# reegan-brd.net
KiCad netlist of a schematic drawn in EAGLE
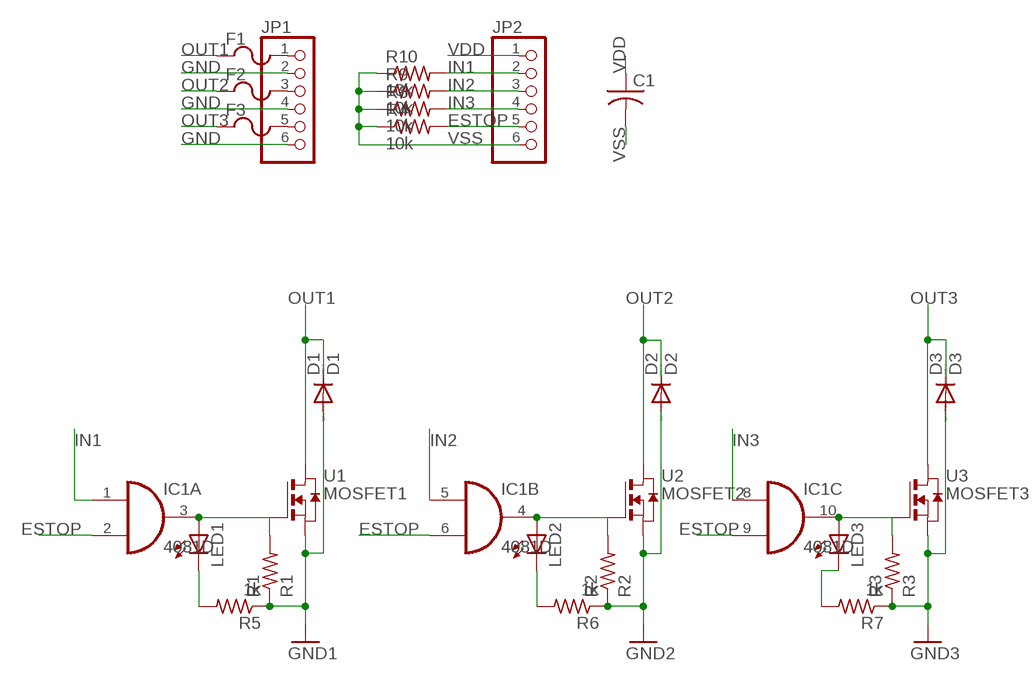
[diagram p0: schematic, sheet 1]

(export (version "E")
  (design (tool "Eeschema 10.0.6"))
  (components
    (comp (ref "C1")
      (value "C-USC0603")
      (footprint "eagle-import:C0603")
      (libsource (lib "eagle-import") (part "C-USC0603"))
    )
    (comp (ref "D1")
      (value "D1")
      (footprint "eagle-import:DO41-10")
      (libsource (lib "eagle-import") (part "1N4004"))
    )
    (comp (ref "D2")
      (value "D2")
      (footprint "eagle-import:DO41-10")
      (libsource (lib "eagle-import") (part "1N4004"))
    )
    (comp (ref "D3")
      (value "D3")
      (footprint "eagle-import:DO41-10")
      (libsource (lib "eagle-import") (part "1N4004"))
    )
    (comp (ref "F1")
      (value "POLYFUSE")
      (footprint "eagle-import:1206")
      (libsource (lib "eagle-import") (part "POLYFUSE"))
    )
    (comp (ref "F2")
      (value "POLYFUSE")
      (footprint "eagle-import:1206")
      (libsource (lib "eagle-import") (part "POLYFUSE"))
    )
    (comp (ref "F3")
      (value "POLYFUSE")
      (footprint "eagle-import:1206")
      (libsource (lib "eagle-import") (part "POLYFUSE"))
    )
    (comp (ref "IC1")
      (value "4081D")
      (footprint "eagle-import:SO14")
      (libsource (lib "eagle-import") (part "4081D"))
    )
    (comp (ref "JP1")
      (value "PINHD-1X6")
      (footprint "eagle-import:1X06")
      (libsource (lib "eagle-import") (part "PINHD-1X6"))
    )
    (comp (ref "JP2")
      (value "PINHD-1X6")
      (footprint "eagle-import:1X06")
      (libsource (lib "eagle-import") (part "PINHD-1X6"))
    )
    (comp (ref "LED1")
      (value "LEDCHIPLED_0603")
      (footprint "eagle-import:CHIPLED_0603")
      (libsource (lib "eagle-import") (part "LEDCHIPLED_0603"))
    )
    (comp (ref "LED2")
      (value "LEDCHIPLED_0603")
      (footprint "eagle-import:CHIPLED_0603")
      (libsource (lib "eagle-import") (part "LEDCHIPLED_0603"))
    )
    (comp (ref "LED3")
      (value "LEDCHIPLED_0603")
      (footprint "eagle-import:CHIPLED_0603")
      (libsource (lib "eagle-import") (part "LEDCHIPLED_0603"))
    )
    (comp (ref "R1")
      (value "R1")
      (footprint "eagle-import:R0603")
      (libsource (lib "eagle-import") (part "resistor_R-US_R0603"))
    )
    (comp (ref "R2")
      (value "R2")
      (footprint "eagle-import:R0603")
      (libsource (lib "eagle-import") (part "resistor_R-US_R0603"))
    )
    (comp (ref "R3")
      (value "R3")
      (footprint "eagle-import:R0603")
      (libsource (lib "eagle-import") (part "resistor_R-US_R0603"))
    )
    (comp (ref "R4")
      (value "10k")
      (footprint "eagle-import:R0603")
      (libsource (lib "eagle-import") (part "R-US_R0603"))
    )
    (comp (ref "R5")
      (value "1k")
      (footprint "eagle-import:R0603")
      (libsource (lib "eagle-import") (part "resistor_R-US_R0603"))
    )
    (comp (ref "R6")
      (value "1k")
      (footprint "eagle-import:R0603")
      (libsource (lib "eagle-import") (part "resistor_R-US_R0603"))
    )
    (comp (ref "R7")
      (value "1k")
      (footprint "eagle-import:R0603")
      (libsource (lib "eagle-import") (part "resistor_R-US_R0603"))
    )
    (comp (ref "R8")
      (value "10k")
      (footprint "eagle-import:R0603")
      (libsource (lib "eagle-import") (part "R-US_R0603"))
    )
    (comp (ref "R9")
      (value "10k")
      (footprint "eagle-import:R0603")
      (libsource (lib "eagle-import") (part "R-US_R0603"))
    )
    (comp (ref "R10")
      (value "10k")
      (footprint "eagle-import:R0603")
      (libsource (lib "eagle-import") (part "R-US_R0603"))
    )
    (comp (ref "U1")
      (value "MOSFET1")
      (footprint "eagle-import:MOSFET")
      (libsource (lib "eagle-import") (part "MOSFET"))
    )
    (comp (ref "U2")
      (value "MOSFET2")
      (footprint "eagle-import:MOSFET")
      (libsource (lib "eagle-import") (part "MOSFET"))
    )
    (comp (ref "U3")
      (value "MOSFET3")
      (footprint "eagle-import:MOSFET")
      (libsource (lib "eagle-import") (part "MOSFET"))
    )
  )
  (nets
    (net (code "1") (name "/ESTOP") (class "Default")
      (node (ref "IC1") (pin "2") (pinfunction "I1_2") (pintype "input"))
      (node (ref "IC1") (pin "6") (pinfunction "I1_6") (pintype "input"))
      (node (ref "IC1") (pin "9") (pinfunction "I1_9") (pintype "input"))
      (node (ref "JP2") (pin "5") (pinfunction "5_5") (pintype "passive"))
      (node (ref "R4") (pin "2") (pinfunction "2_2") (pintype "passive"))
    )
    (net (code "2") (name "/IN1") (class "Default")
      (node (ref "IC1") (pin "1") (pinfunction "I0_1") (pintype "input"))
      (node (ref "JP2") (pin "2") (pinfunction "2_2") (pintype "passive"))
      (node (ref "R10") (pin "2") (pinfunction "2_2") (pintype "passive"))
    )
    (net (code "3") (name "/IN2") (class "Default")
      (node (ref "IC1") (pin "5") (pinfunction "I0_5") (pintype "input"))
      (node (ref "JP2") (pin "3") (pinfunction "3_3") (pintype "passive"))
      (node (ref "R9") (pin "2") (pinfunction "2_2") (pintype "passive"))
    )
    (net (code "4") (name "/IN3") (class "Default")
      (node (ref "IC1") (pin "8") (pinfunction "I0_8") (pintype "input"))
      (node (ref "JP2") (pin "4") (pinfunction "4_4") (pintype "passive"))
      (node (ref "R8") (pin "2") (pinfunction "2_2") (pintype "passive"))
    )
    (net (code "5") (name "/OUT1") (class "Default")
      (node (ref "D1") (pin "C") (pinfunction "C_C") (pintype "passive"))
      (node (ref "F1") (pin "1") (pinfunction "1_1") (pintype "passive"))
      (node (ref "U1") (pin "P$2") (pinfunction "D_P$2") (pintype "passive"))
    )
    (net (code "6") (name "/OUT2") (class "Default")
      (node (ref "D2") (pin "C") (pinfunction "C_C") (pintype "passive"))
      (node (ref "F2") (pin "1") (pinfunction "1_1") (pintype "passive"))
      (node (ref "U2") (pin "P$2") (pinfunction "D_P$2") (pintype "passive"))
    )
    (net (code "7") (name "/OUT3") (class "Default")
      (node (ref "D3") (pin "C") (pinfunction "C_C") (pintype "passive"))
      (node (ref "F3") (pin "1") (pinfunction "1_1") (pintype "passive"))
      (node (ref "U3") (pin "P$2") (pinfunction "D_P$2") (pintype "passive"))
    )
    (net (code "8") (name "/VDD") (class "Default")
      (node (ref "C1") (pin "1") (pinfunction "1_1") (pintype "passive"))
      (node (ref "JP2") (pin "1") (pinfunction "1_1") (pintype "passive"))
    )
    (net (code "9") (name "/VSS") (class "Default")
      (node (ref "C1") (pin "2") (pinfunction "2_2") (pintype "passive"))
      (node (ref "JP2") (pin "6") (pinfunction "6_6") (pintype "passive"))
      (node (ref "R10") (pin "1") (pinfunction "1_1") (pintype "passive"))
      (node (ref "R4") (pin "1") (pinfunction "1_1") (pintype "passive"))
      (node (ref "R8") (pin "1") (pinfunction "1_1") (pintype "passive"))
      (node (ref "R9") (pin "1") (pinfunction "1_1") (pintype "passive"))
    )
    (net (code "10") (name "GND1") (class "Default")
      (node (ref "D1") (pin "A") (pinfunction "A_A") (pintype "passive"))
      (node (ref "D2") (pin "A") (pinfunction "A_A") (pintype "passive"))
      (node (ref "D3") (pin "A") (pinfunction "A_A") (pintype "passive"))
      (node (ref "JP1") (pin "2") (pinfunction "2_2") (pintype "passive"))
      (node (ref "JP1") (pin "4") (pinfunction "4_4") (pintype "passive"))
      (node (ref "JP1") (pin "6") (pinfunction "6_6") (pintype "passive"))
      (node (ref "R1") (pin "1") (pinfunction "1_1") (pintype "passive"))
      (node (ref "R2") (pin "1") (pinfunction "1_1") (pintype "passive"))
      (node (ref "R3") (pin "1") (pinfunction "1_1") (pintype "passive"))
      (node (ref "R5") (pin "1") (pinfunction "1_1") (pintype "passive"))
      (node (ref "R6") (pin "1") (pinfunction "1_1") (pintype "passive"))
      (node (ref "R7") (pin "1") (pinfunction "1_1") (pintype "passive"))
      (node (ref "U1") (pin "P$3") (pinfunction "S_P$3") (pintype "passive"))
      (node (ref "U2") (pin "P$3") (pinfunction "S_P$3") (pintype "passive"))
      (node (ref "U3") (pin "P$3") (pinfunction "S_P$3") (pintype "passive"))
    )
    (net (code "11") (name "Net-(F1-Pad2)") (class "Default")
      (node (ref "F1") (pin "2") (pinfunction "2_2") (pintype "passive"))
      (node (ref "JP1") (pin "1") (pinfunction "1_1") (pintype "passive"))
    )
    (net (code "12") (name "Net-(F2-Pad2)") (class "Default")
      (node (ref "F2") (pin "2") (pinfunction "2_2") (pintype "passive"))
      (node (ref "JP1") (pin "3") (pinfunction "3_3") (pintype "passive"))
    )
    (net (code "13") (name "Net-(F3-Pad2)") (class "Default")
      (node (ref "F3") (pin "2") (pinfunction "2_2") (pintype "passive"))
      (node (ref "JP1") (pin "5") (pinfunction "5_5") (pintype "passive"))
    )
    (net (code "14") (name "Net-(IC1A-O)") (class "Default")
      (node (ref "IC1") (pin "3") (pinfunction "O_3") (pintype "output"))
      (node (ref "LED1") (pin "A") (pinfunction "A_A") (pintype "passive"))
      (node (ref "R1") (pin "2") (pinfunction "2_2") (pintype "passive"))
      (node (ref "U1") (pin "P$1") (pinfunction "G_P$1") (pintype "passive"))
    )
    (net (code "15") (name "Net-(IC1B-O)") (class "Default")
      (node (ref "IC1") (pin "4") (pinfunction "O_4") (pintype "output"))
      (node (ref "LED2") (pin "A") (pinfunction "A_A") (pintype "passive"))
      (node (ref "R2") (pin "2") (pinfunction "2_2") (pintype "passive"))
      (node (ref "U2") (pin "P$1") (pinfunction "G_P$1") (pintype "passive"))
    )
    (net (code "16") (name "Net-(IC1C-O)") (class "Default")
      (node (ref "IC1") (pin "10") (pinfunction "O_10") (pintype "output"))
      (node (ref "LED3") (pin "A") (pinfunction "A_A") (pintype "passive"))
      (node (ref "R3") (pin "2") (pinfunction "2_2") (pintype "passive"))
      (node (ref "U3") (pin "P$1") (pinfunction "G_P$1") (pintype "passive"))
    )
    (net (code "17") (name "Net-(LED1-PadC)") (class "Default")
      (node (ref "LED1") (pin "C") (pinfunction "C_C") (pintype "passive"))
      (node (ref "R5") (pin "2") (pinfunction "2_2") (pintype "passive"))
    )
    (net (code "18") (name "Net-(LED2-PadC)") (class "Default")
      (node (ref "LED2") (pin "C") (pinfunction "C_C") (pintype "passive"))
      (node (ref "R6") (pin "2") (pinfunction "2_2") (pintype "passive"))
    )
    (net (code "19") (name "Net-(LED3-PadC)") (class "Default")
      (node (ref "LED3") (pin "C") (pinfunction "C_C") (pintype "passive"))
      (node (ref "R7") (pin "2") (pinfunction "2_2") (pintype "passive"))
    )
  )
)
